# AD9959.net
KiCad netlist of a schematic drawn in Altium Designer
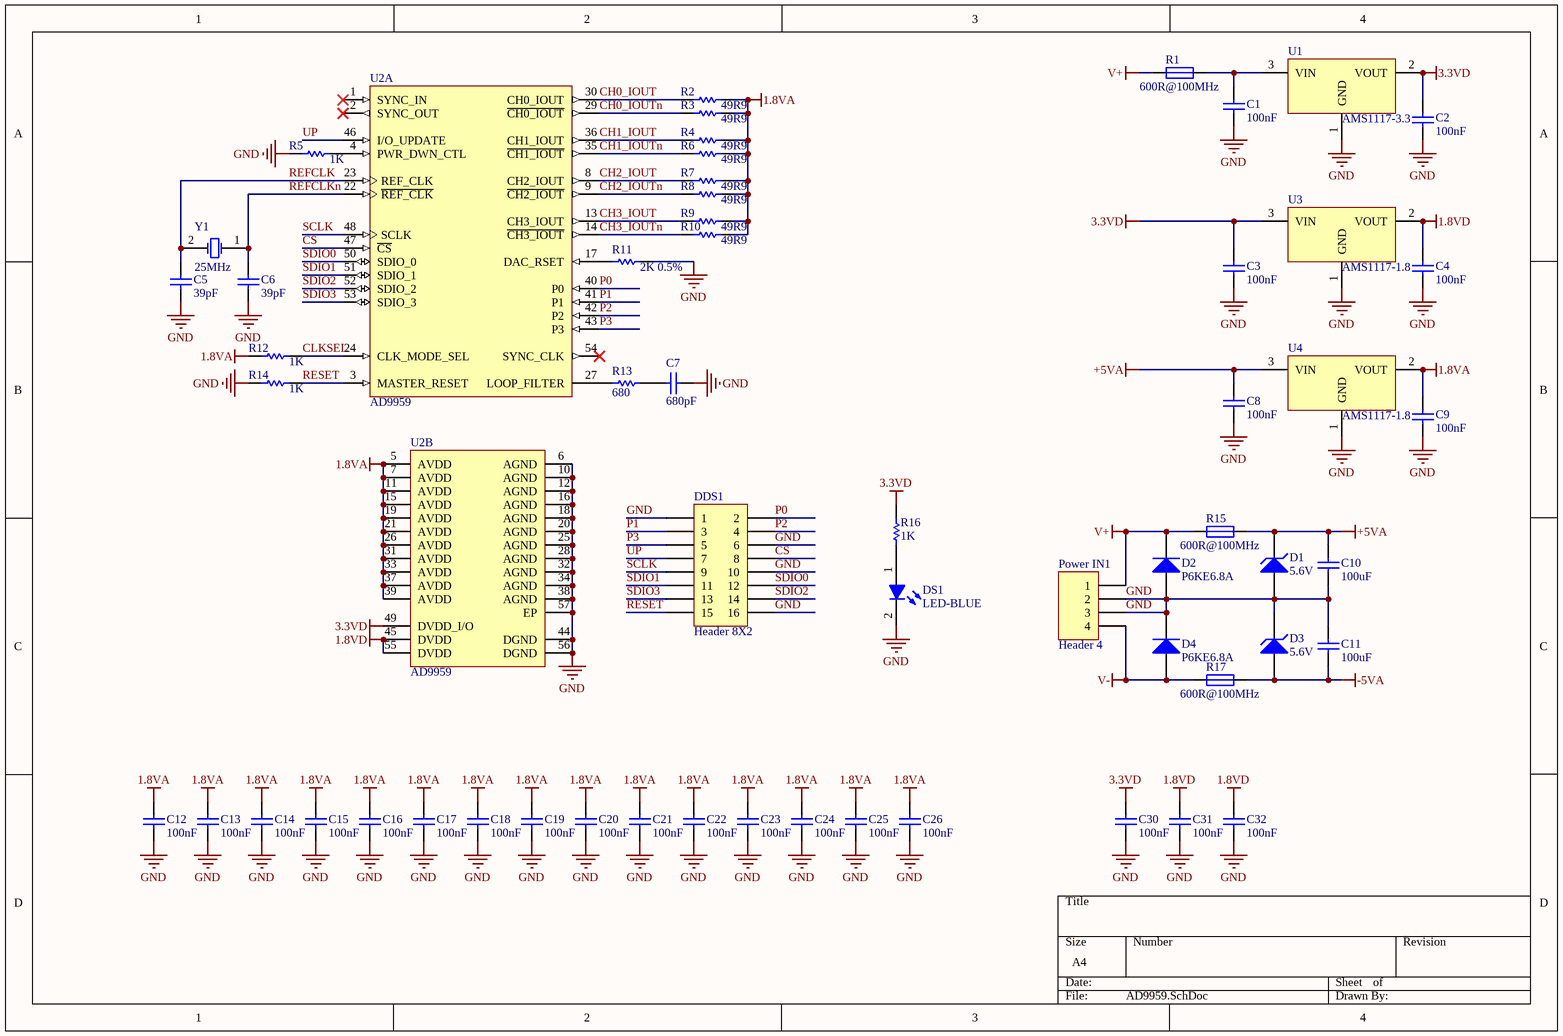
[diagram p0: AD9959.SchDoc]

(export (version "E")
  (design (tool "Eeschema 10.0.6"))
  (components
    (comp (ref "C1")
      (value "100nF")
      (footprint "CAPC0603(1608)55_M")
      (libsource (lib "Slivy's Library") (part "CAP"))
    )
    (comp (ref "C2")
      (value "100nF")
      (footprint "CAPC0603(1608)55_M")
      (libsource (lib "Slivy's Library") (part "CAP"))
    )
    (comp (ref "C3")
      (value "100nF")
      (footprint "CAPC0603(1608)55_M")
      (libsource (lib "Slivy's Library") (part "CAP"))
    )
    (comp (ref "C4")
      (value "100nF")
      (footprint "CAPC0603(1608)55_M")
      (libsource (lib "Slivy's Library") (part "CAP"))
    )
    (comp (ref "C5")
      (value "39pF")
      (footprint "CAPC0603(1608)55_M")
      (libsource (lib "Slivy's Library") (part "CAP"))
    )
    (comp (ref "C6")
      (value "39pF")
      (footprint "CAPC0603(1608)55_M")
      (libsource (lib "Slivy's Library") (part "CAP"))
    )
    (comp (ref "C7")
      (value "680pF")
      (footprint "CAPC0603(1608)55_M")
      (libsource (lib "Slivy's Library") (part "CAP"))
    )
    (comp (ref "C8")
      (value "100nF")
      (footprint "CAPC0603(1608)55_M")
      (libsource (lib "Slivy's Library") (part "CAP"))
    )
    (comp (ref "C9")
      (value "100nF")
      (footprint "CAPC0603(1608)55_M")
      (libsource (lib "Slivy's Library") (part "CAP"))
    )
    (comp (ref "C10") (value "100uF") (footprint "CAPC3225") (libsource (lib "Slivy's Library") (part "CAP")))
    (comp (ref "C11") (value "100uF") (footprint "CAPC3225") (libsource (lib "Slivy's Library") (part "CAP")))
    (comp (ref "C12")
      (value "100nF")
      (footprint "CAPC0603(1608)55_M")
      (libsource (lib "Slivy's Library") (part "CAP"))
    )
    (comp (ref "C13")
      (value "100nF")
      (footprint "CAPC0603(1608)55_M")
      (libsource (lib "Slivy's Library") (part "CAP"))
    )
    (comp (ref "C14")
      (value "100nF")
      (footprint "CAPC0603(1608)55_M")
      (libsource (lib "Slivy's Library") (part "CAP"))
    )
    (comp (ref "C15")
      (value "100nF")
      (footprint "CAPC0603(1608)55_M")
      (libsource (lib "Slivy's Library") (part "CAP"))
    )
    (comp (ref "C16")
      (value "100nF")
      (footprint "CAPC0603(1608)55_M")
      (libsource (lib "Slivy's Library") (part "CAP"))
    )
    (comp (ref "C17")
      (value "100nF")
      (footprint "CAPC0603(1608)55_M")
      (libsource (lib "Slivy's Library") (part "CAP"))
    )
    (comp (ref "C18")
      (value "100nF")
      (footprint "CAPC0603(1608)55_M")
      (libsource (lib "Slivy's Library") (part "CAP"))
    )
    (comp (ref "C19")
      (value "100nF")
      (footprint "CAPC0603(1608)55_M")
      (libsource (lib "Slivy's Library") (part "CAP"))
    )
    (comp (ref "C20")
      (value "100nF")
      (footprint "CAPC0603(1608)55_M")
      (libsource (lib "Slivy's Library") (part "CAP"))
    )
    (comp (ref "C21")
      (value "100nF")
      (footprint "CAPC0603(1608)55_M")
      (libsource (lib "Slivy's Library") (part "CAP"))
    )
    (comp (ref "C22")
      (value "100nF")
      (footprint "CAPC0603(1608)55_M")
      (libsource (lib "Slivy's Library") (part "CAP"))
    )
    (comp (ref "C23")
      (value "100nF")
      (footprint "CAPC0603(1608)55_M")
      (libsource (lib "Slivy's Library") (part "CAP"))
    )
    (comp (ref "C24")
      (value "100nF")
      (footprint "CAPC0603(1608)55_M")
      (libsource (lib "Slivy's Library") (part "CAP"))
    )
    (comp (ref "C25")
      (value "100nF")
      (footprint "CAPC0603(1608)55_M")
      (libsource (lib "Slivy's Library") (part "CAP"))
    )
    (comp (ref "C26")
      (value "100nF")
      (footprint "CAPC0603(1608)55_M")
      (libsource (lib "Slivy's Library") (part "CAP"))
    )
    (comp (ref "C30")
      (value "100nF")
      (footprint "CAPC0603(1608)55_M")
      (libsource (lib "Slivy's Library") (part "CAP"))
    )
    (comp (ref "C31")
      (value "100nF")
      (footprint "CAPC0603(1608)55_M")
      (libsource (lib "Slivy's Library") (part "CAP"))
    )
    (comp (ref "C32")
      (value "100nF")
      (footprint "CAPC0603(1608)55_M")
      (libsource (lib "Slivy's Library") (part "CAP"))
    )
    (comp (ref "D1")
      (value "5.6V")
      (footprint "LL34")
      (description "Zener Diode")
      (fields (field (name "PUBLISHER") "Altium Limited"))
      (libsource (lib "Miscellaneous Devices") (part "D Zener"))
    )
    (comp (ref "D2")
      (value "P6KE6.8A")
      (footprint "DO-214AC")
      (libsource (lib "Slivy's ibrary") (part "Diode"))
    )
    (comp (ref "D3")
      (value "5.6V")
      (footprint "LL34")
      (description "Zener Diode")
      (fields (field (name "PUBLISHER") "Altium Limited"))
      (libsource (lib "Miscellaneous Devices") (part "D Zener"))
    )
    (comp (ref "D4")
      (value "P6KE6.8A")
      (footprint "DO-214AC")
      (libsource (lib "Slivy's ibrary") (part "Diode"))
    )
    (comp (ref "DDS1")
      (value "Header 8X2")
      (footprint "HEADER8X2")
      (description "Header, 8-Pin, Dual row")
      (fields (field (name "PUBLISHER") "Altium Limited"))
      (libsource (lib "Miscellaneous Connectors") (part "Header 8X2"))
    )
    (comp (ref "DS1")
      (value "LED-BLUE")
      (footprint "0603LED_BLUE_V")
      (libsource (lib "Slivy's ibrary") (part "LED-BLUE"))
    )
    (comp (ref "Power IN1")
      (value "Header 4")
      (footprint "3.96-4")
      (description "Header, 4-Pin")
      (fields (field (name "PUBLISHER") "Altium Limited"))
      (libsource (lib "Miscellaneous Connectors") (part "Header 4"))
    )
    (comp (ref "R1")
      (value "600R@100MHz")
      (footprint "Slivy's Library:RESC1206(3216)_M")
      (description "Ferrite Bead")
      (fields
        (field (name "MANUFACTURER") "Generic Components")
        (field (name "PUBLISHER") "Altium Hobart Technology Centre")
      )
      (libsource (lib "Integrated_Library1") (part "Ferrite Bead"))
    )
    (comp (ref "R2")
      (value "49R9")
      (footprint "RESC0603(1608)_M")
      (libsource (lib "Slivy's Library") (part "RES"))
    )
    (comp (ref "R3")
      (value "49R9")
      (footprint "RESC0603(1608)_M")
      (libsource (lib "Slivy's Library") (part "RES"))
    )
    (comp (ref "R4")
      (value "49R9")
      (footprint "RESC0603(1608)_M")
      (libsource (lib "Slivy's Library") (part "RES"))
    )
    (comp (ref "R5")
      (value "1K")
      (footprint "RESC0603(1608)_M")
      (libsource (lib "Slivy's Library") (part "RES"))
    )
    (comp (ref "R6")
      (value "49R9")
      (footprint "RESC0603(1608)_M")
      (libsource (lib "Slivy's Library") (part "RES"))
    )
    (comp (ref "R7")
      (value "49R9")
      (footprint "RESC0603(1608)_M")
      (libsource (lib "Slivy's Library") (part "RES"))
    )
    (comp (ref "R8")
      (value "49R9")
      (footprint "RESC0603(1608)_M")
      (libsource (lib "Slivy's Library") (part "RES"))
    )
    (comp (ref "R9")
      (value "49R9")
      (footprint "RESC0603(1608)_M")
      (libsource (lib "Slivy's Library") (part "RES"))
    )
    (comp (ref "R10")
      (value "49R9")
      (footprint "RESC0603(1608)_M")
      (libsource (lib "Slivy's Library") (part "RES"))
    )
    (comp (ref "R11")
      (value "2K 0.5%")
      (footprint "RESC0603(1608)_M")
      (libsource (lib "Slivy's Library") (part "RES"))
    )
    (comp (ref "R12")
      (value "1K")
      (footprint "RESC0603(1608)_M")
      (libsource (lib "Slivy's Library") (part "RES"))
    )
    (comp (ref "R13")
      (value "680")
      (footprint "RESC0603(1608)_M")
      (libsource (lib "Slivy's Library") (part "RES"))
    )
    (comp (ref "R14")
      (value "1K")
      (footprint "RESC0603(1608)_M")
      (libsource (lib "Slivy's Library") (part "RES"))
    )
    (comp (ref "R15")
      (value "600R@100MHz")
      (footprint "Slivy's Library:RESC1206(3216)_M")
      (description "Ferrite Bead")
      (fields
        (field (name "MANUFACTURER") "Generic Components")
        (field (name "PUBLISHER") "Altium Hobart Technology Centre")
      )
      (libsource (lib "Integrated_Library1") (part "Ferrite Bead"))
    )
    (comp (ref "R16")
      (value "1K")
      (footprint "RESC0603(1608)_M")
      (libsource (lib "Slivy's Library") (part "RES"))
    )
    (comp (ref "R17")
      (value "600R@100MHz")
      (footprint "RESC1206(3216)_M")
      (description "Ferrite Bead")
      (fields
        (field (name "MANUFACTURER") "Generic Components")
        (field (name "PUBLISHER") "Altium Hobart Technology Centre")
      )
      (libsource (lib "Integrated_Library1") (part "Ferrite Bead"))
    )
    (comp (ref "U1")
      (value "AMS1117-3.3")
      (footprint "SOT-223_M")
      (libsource (lib "Slivy's ibrary") (part "AMS1117"))
    )
    (comp (ref "U2") (value "AD9959") (footprint "QFN56") (libsource (lib "Slivy's ibrary") (part "AD9959")))
    (comp (ref "U3")
      (value "AMS1117-1.8")
      (footprint "SOT-223_M")
      (libsource (lib "Slivy's ibrary") (part "AMS1117"))
    )
    (comp (ref "U4")
      (value "AMS1117-1.8")
      (footprint "SOT-223_M")
      (libsource (lib "Slivy's ibrary") (part "AMS1117"))
    )
    (comp (ref "Y1")
      (value "25MHz")
      (footprint "HC-49S")
      (description "Crystal Oscillator")
      (fields (field (name "PUBLISHER") "Altium Limited"))
      (libsource (lib "Slivy's ibrary") (part "XTAL"))
    )
  )
  (nets
    (net (code "1") (name "+5VA") (class "Default")
      (node (ref "C10") (pin "2") (pinfunction "2_2") (pintype "passive"))
      (node (ref "C8") (pin "2") (pinfunction "2_2") (pintype "passive"))
      (node (ref "D1") (pin "2") (pinfunction "K_2") (pintype "passive"))
      (node (ref "R15") (pin "2") (pinfunction "2_2") (pintype "passive"))
      (node (ref "U4") (pin "3") (pinfunction "VIN_3") (pintype "power_in"))
    )
    (net (code "2") (name "-5VA") (class "Default")
      (node (ref "C11") (pin "2") (pinfunction "2_2") (pintype "passive"))
      (node (ref "D3") (pin "1") (pinfunction "A_1") (pintype "passive"))
      (node (ref "R17") (pin "2") (pinfunction "2_2") (pintype "passive"))
    )
    (net (code "3") (name "/CH0_IOUT") (class "Default")
      (node (ref "R2") (pin "1") (pinfunction "1_1") (pintype "passive"))
      (node (ref "U2") (pin "30") (pinfunction "CH0_IOUT_30") (pintype "output"))
    )
    (net (code "4") (name "/CH0_IOUTn") (class "Default")
      (node (ref "R3") (pin "1") (pinfunction "1_1") (pintype "passive"))
      (node (ref "U2") (pin "29") (pinfunction "~{CH0_IOUT}_29") (pintype "output"))
    )
    (net (code "5") (name "/CH1_IOUT") (class "Default")
      (node (ref "R4") (pin "1") (pinfunction "1_1") (pintype "passive"))
      (node (ref "U2") (pin "36") (pinfunction "CH1_IOUT_36") (pintype "output"))
    )
    (net (code "6") (name "/CH1_IOUTn") (class "Default")
      (node (ref "R6") (pin "1") (pinfunction "1_1") (pintype "passive"))
      (node (ref "U2") (pin "35") (pinfunction "~{CH1_IOUT}_35") (pintype "output"))
    )
    (net (code "7") (name "/CH2_IOUT") (class "Default")
      (node (ref "R7") (pin "1") (pinfunction "1_1") (pintype "passive"))
      (node (ref "U2") (pin "8") (pinfunction "CH2_IOUT_8") (pintype "output"))
    )
    (net (code "8") (name "/CH2_IOUTn") (class "Default")
      (node (ref "R8") (pin "1") (pinfunction "1_1") (pintype "passive"))
      (node (ref "U2") (pin "9") (pinfunction "~{CH2_IOUT}_9") (pintype "output"))
    )
    (net (code "9") (name "/CH3_IOUT") (class "Default")
      (node (ref "R9") (pin "1") (pinfunction "1_1") (pintype "passive"))
      (node (ref "U2") (pin "13") (pinfunction "CH3_IOUT_13") (pintype "output"))
    )
    (net (code "10") (name "/CH3_IOUTn") (class "Default")
      (node (ref "R10") (pin "1") (pinfunction "1_1") (pintype "passive"))
      (node (ref "U2") (pin "14") (pinfunction "~{CH3_IOUT}_14") (pintype "output"))
    )
    (net (code "11") (name "/CLKSEL") (class "Default")
      (node (ref "R12") (pin "2") (pinfunction "2_2") (pintype "passive"))
      (node (ref "U2") (pin "24") (pinfunction "CLK_MODE_SEL_24") (pintype "input"))
    )
    (net (code "12") (name "/CS") (class "Default")
      (node (ref "DDS1") (pin "8") (pinfunction "8_8") (pintype "passive"))
      (node (ref "U2") (pin "47") (pinfunction "~{CS}_47") (pintype "input"))
    )
    (net (code "13") (name "/P0") (class "Default")
      (node (ref "DDS1") (pin "2") (pinfunction "2_2") (pintype "passive"))
      (node (ref "U2") (pin "40") (pinfunction "P0_40") (pintype "input"))
    )
    (net (code "14") (name "/P1") (class "Default")
      (node (ref "DDS1") (pin "3") (pinfunction "3_3") (pintype "passive"))
      (node (ref "U2") (pin "41") (pinfunction "P1_41") (pintype "input"))
    )
    (net (code "15") (name "/P2") (class "Default")
      (node (ref "DDS1") (pin "4") (pinfunction "4_4") (pintype "passive"))
      (node (ref "U2") (pin "42") (pinfunction "P2_42") (pintype "input"))
    )
    (net (code "16") (name "/P3") (class "Default")
      (node (ref "DDS1") (pin "5") (pinfunction "5_5") (pintype "passive"))
      (node (ref "U2") (pin "43") (pinfunction "P3_43") (pintype "input"))
    )
    (net (code "17") (name "/REFCLK") (class "Default")
      (node (ref "C5") (pin "2") (pinfunction "2_2") (pintype "passive"))
      (node (ref "U2") (pin "23") (pinfunction "REF_CLK_23") (pintype "input"))
      (node (ref "Y1") (pin "2") (pinfunction "OSC2_2") (pintype "passive"))
    )
    (net (code "18") (name "/REFCLKn") (class "Default")
      (node (ref "C6") (pin "2") (pinfunction "2_2") (pintype "passive"))
      (node (ref "U2") (pin "22") (pinfunction "~{REF_CLK}_22") (pintype "input"))
      (node (ref "Y1") (pin "1") (pinfunction "OSC1_1") (pintype "passive"))
    )
    (net (code "19") (name "/RESET") (class "Default")
      (node (ref "DDS1") (pin "15") (pinfunction "15_15") (pintype "passive"))
      (node (ref "R14") (pin "2") (pinfunction "2_2") (pintype "passive"))
      (node (ref "U2") (pin "3") (pinfunction "MASTER_RESET_3") (pintype "input"))
    )
    (net (code "20") (name "/SCLK") (class "Default")
      (node (ref "DDS1") (pin "9") (pinfunction "9_9") (pintype "passive"))
      (node (ref "U2") (pin "48") (pinfunction "SCLK_48") (pintype "input"))
    )
    (net (code "21") (name "/SDIO0") (class "Default")
      (node (ref "DDS1") (pin "12") (pinfunction "12_12") (pintype "passive"))
      (node (ref "U2") (pin "50") (pinfunction "SDIO_0_50") (pintype "bidirectional"))
    )
    (net (code "22") (name "/SDIO1") (class "Default")
      (node (ref "DDS1") (pin "11") (pinfunction "11_11") (pintype "passive"))
      (node (ref "U2") (pin "51") (pinfunction "SDIO_1_51") (pintype "bidirectional"))
    )
    (net (code "23") (name "/SDIO2") (class "Default")
      (node (ref "DDS1") (pin "14") (pinfunction "14_14") (pintype "passive"))
      (node (ref "U2") (pin "52") (pinfunction "SDIO_2_52") (pintype "bidirectional"))
    )
    (net (code "24") (name "/SDIO3") (class "Default")
      (node (ref "DDS1") (pin "13") (pinfunction "13_13") (pintype "passive"))
      (node (ref "U2") (pin "53") (pinfunction "SDIO_3_53") (pintype "bidirectional"))
    )
    (net (code "25") (name "/UP") (class "Default")
      (node (ref "DDS1") (pin "7") (pinfunction "7_7") (pintype "passive"))
      (node (ref "U2") (pin "46") (pinfunction "I/O_UPDATE_46") (pintype "input"))
    )
    (net (code "26") (name "1.8VA") (class "Default")
      (node (ref "C12") (pin "2") (pinfunction "2_2") (pintype "passive"))
      (node (ref "C13") (pin "2") (pinfunction "2_2") (pintype "passive"))
      (node (ref "C14") (pin "2") (pinfunction "2_2") (pintype "passive"))
      (node (ref "C15") (pin "2") (pinfunction "2_2") (pintype "passive"))
      (node (ref "C16") (pin "2") (pinfunction "2_2") (pintype "passive"))
      (node (ref "C17") (pin "2") (pinfunction "2_2") (pintype "passive"))
      (node (ref "C18") (pin "2") (pinfunction "2_2") (pintype "passive"))
      (node (ref "C19") (pin "2") (pinfunction "2_2") (pintype "passive"))
      (node (ref "C20") (pin "2") (pinfunction "2_2") (pintype "passive"))
      (node (ref "C21") (pin "2") (pinfunction "2_2") (pintype "passive"))
      (node (ref "C22") (pin "2") (pinfunction "2_2") (pintype "passive"))
      (node (ref "C23") (pin "2") (pinfunction "2_2") (pintype "passive"))
      (node (ref "C24") (pin "2") (pinfunction "2_2") (pintype "passive"))
      (node (ref "C25") (pin "2") (pinfunction "2_2") (pintype "passive"))
      (node (ref "C26") (pin "2") (pinfunction "2_2") (pintype "passive"))
      (node (ref "C9") (pin "2") (pinfunction "2_2") (pintype "passive"))
      (node (ref "R10") (pin "2") (pinfunction "2_2") (pintype "passive"))
      (node (ref "R12") (pin "1") (pinfunction "1_1") (pintype "passive"))
      (node (ref "R2") (pin "2") (pinfunction "2_2") (pintype "passive"))
      (node (ref "R3") (pin "2") (pinfunction "2_2") (pintype "passive"))
      (node (ref "R4") (pin "2") (pinfunction "2_2") (pintype "passive"))
      (node (ref "R6") (pin "2") (pinfunction "2_2") (pintype "passive"))
      (node (ref "R7") (pin "2") (pinfunction "2_2") (pintype "passive"))
      (node (ref "R8") (pin "2") (pinfunction "2_2") (pintype "passive"))
      (node (ref "R9") (pin "2") (pinfunction "2_2") (pintype "passive"))
      (node (ref "U2") (pin "11") (pinfunction "AVDD_11") (pintype "power_in"))
      (node (ref "U2") (pin "15") (pinfunction "AVDD_15") (pintype "power_in"))
      (node (ref "U2") (pin "19") (pinfunction "AVDD_19") (pintype "power_in"))
      (node (ref "U2") (pin "21") (pinfunction "AVDD_21") (pintype "power_in"))
      (node (ref "U2") (pin "26") (pinfunction "AVDD_26") (pintype "power_in"))
      (node (ref "U2") (pin "31") (pinfunction "AVDD_31") (pintype "power_in"))
      (node (ref "U2") (pin "33") (pinfunction "AVDD_33") (pintype "power_in"))
      (node (ref "U2") (pin "37") (pinfunction "AVDD_37") (pintype "power_in"))
      (node (ref "U2") (pin "39") (pinfunction "AVDD_39") (pintype "power_in"))
      (node (ref "U2") (pin "5") (pinfunction "AVDD_5") (pintype "power_in"))
      (node (ref "U2") (pin "7") (pinfunction "AVDD_7") (pintype "power_in"))
      (node (ref "U4") (pin "2") (pinfunction "VOUT_2") (pintype "power_in"))
    )
    (net (code "27") (name "1.8VD") (class "Default")
      (node (ref "C31") (pin "2") (pinfunction "2_2") (pintype "passive"))
      (node (ref "C32") (pin "2") (pinfunction "2_2") (pintype "passive"))
      (node (ref "C4") (pin "2") (pinfunction "2_2") (pintype "passive"))
      (node (ref "U2") (pin "45") (pinfunction "DVDD_45") (pintype "power_in"))
      (node (ref "U2") (pin "55") (pinfunction "DVDD_55") (pintype "power_in"))
      (node (ref "U3") (pin "2") (pinfunction "VOUT_2") (pintype "power_in"))
    )
    (net (code "28") (name "3.3VD") (class "Default")
      (node (ref "C2") (pin "2") (pinfunction "2_2") (pintype "passive"))
      (node (ref "C3") (pin "2") (pinfunction "2_2") (pintype "passive"))
      (node (ref "C30") (pin "2") (pinfunction "2_2") (pintype "passive"))
      (node (ref "R16") (pin "2") (pinfunction "2_2") (pintype "passive"))
      (node (ref "U1") (pin "2") (pinfunction "VOUT_2") (pintype "power_in"))
      (node (ref "U2") (pin "49") (pinfunction "DVDD_I/O_49") (pintype "power_in"))
      (node (ref "U3") (pin "3") (pinfunction "VIN_3") (pintype "power_in"))
    )
    (net (code "29") (name "GND") (class "Default")
      (node (ref "C1") (pin "1") (pinfunction "1_1") (pintype "passive"))
      (node (ref "C10") (pin "1") (pinfunction "1_1") (pintype "passive"))
      (node (ref "C11") (pin "1") (pinfunction "1_1") (pintype "passive"))
      (node (ref "C12") (pin "1") (pinfunction "1_1") (pintype "passive"))
      (node (ref "C13") (pin "1") (pinfunction "1_1") (pintype "passive"))
      (node (ref "C14") (pin "1") (pinfunction "1_1") (pintype "passive"))
      (node (ref "C15") (pin "1") (pinfunction "1_1") (pintype "passive"))
      (node (ref "C16") (pin "1") (pinfunction "1_1") (pintype "passive"))
      (node (ref "C17") (pin "1") (pinfunction "1_1") (pintype "passive"))
      (node (ref "C18") (pin "1") (pinfunction "1_1") (pintype "passive"))
      (node (ref "C19") (pin "1") (pinfunction "1_1") (pintype "passive"))
      (node (ref "C2") (pin "1") (pinfunction "1_1") (pintype "passive"))
      (node (ref "C20") (pin "1") (pinfunction "1_1") (pintype "passive"))
      (node (ref "C21") (pin "1") (pinfunction "1_1") (pintype "passive"))
      (node (ref "C22") (pin "1") (pinfunction "1_1") (pintype "passive"))
      (node (ref "C23") (pin "1") (pinfunction "1_1") (pintype "passive"))
      (node (ref "C24") (pin "1") (pinfunction "1_1") (pintype "passive"))
      (node (ref "C25") (pin "1") (pinfunction "1_1") (pintype "passive"))
      (node (ref "C26") (pin "1") (pinfunction "1_1") (pintype "passive"))
      (node (ref "C3") (pin "1") (pinfunction "1_1") (pintype "passive"))
      (node (ref "C30") (pin "1") (pinfunction "1_1") (pintype "passive"))
      (node (ref "C31") (pin "1") (pinfunction "1_1") (pintype "passive"))
      (node (ref "C32") (pin "1") (pinfunction "1_1") (pintype "passive"))
      (node (ref "C4") (pin "1") (pinfunction "1_1") (pintype "passive"))
      (node (ref "C5") (pin "1") (pinfunction "1_1") (pintype "passive"))
      (node (ref "C6") (pin "1") (pinfunction "1_1") (pintype "passive"))
      (node (ref "C7") (pin "2") (pinfunction "2_2") (pintype "passive"))
      (node (ref "C8") (pin "1") (pinfunction "1_1") (pintype "passive"))
      (node (ref "C9") (pin "1") (pinfunction "1_1") (pintype "passive"))
      (node (ref "D1") (pin "1") (pinfunction "A_1") (pintype "passive"))
      (node (ref "D2") (pin "2") (pinfunction "A_2") (pintype "passive"))
      (node (ref "D3") (pin "2") (pinfunction "K_2") (pintype "passive"))
      (node (ref "D4") (pin "1") (pinfunction "K_1") (pintype "passive"))
      (node (ref "DDS1") (pin "1") (pinfunction "1_1") (pintype "passive"))
      (node (ref "DDS1") (pin "10") (pinfunction "10_10") (pintype "passive"))
      (node (ref "DDS1") (pin "16") (pinfunction "16_16") (pintype "passive"))
      (node (ref "DDS1") (pin "6") (pinfunction "6_6") (pintype "passive"))
      (node (ref "DS1") (pin "2") (pinfunction "K_2") (pintype "passive"))
      (node (ref "Power IN1") (pin "2") (pinfunction "2_2") (pintype "passive"))
      (node (ref "Power IN1") (pin "3") (pinfunction "3_3") (pintype "passive"))
      (node (ref "R11") (pin "2") (pinfunction "2_2") (pintype "passive"))
      (node (ref "R14") (pin "1") (pinfunction "1_1") (pintype "passive"))
      (node (ref "R5") (pin "1") (pinfunction "1_1") (pintype "passive"))
      (node (ref "U1") (pin "1") (pinfunction "GND_1") (pintype "power_in"))
      (node (ref "U2") (pin "10") (pinfunction "AGND_10") (pintype "power_in"))
      (node (ref "U2") (pin "12") (pinfunction "AGND_12") (pintype "power_in"))
      (node (ref "U2") (pin "16") (pinfunction "AGND_16") (pintype "power_in"))
      (node (ref "U2") (pin "18") (pinfunction "AGND_18") (pintype "power_in"))
      (node (ref "U2") (pin "20") (pinfunction "AGND_20") (pintype "power_in"))
      (node (ref "U2") (pin "25") (pinfunction "AGND_25") (pintype "power_in"))
      (node (ref "U2") (pin "28") (pinfunction "AGND_28") (pintype "power_in"))
      (node (ref "U2") (pin "32") (pinfunction "AGND_32") (pintype "power_in"))
      (node (ref "U2") (pin "34") (pinfunction "AGND_34") (pintype "power_in"))
      (node (ref "U2") (pin "38") (pinfunction "AGND_38") (pintype "power_in"))
      (node (ref "U2") (pin "44") (pinfunction "DGND_44") (pintype "power_in"))
      (node (ref "U2") (pin "56") (pinfunction "DGND_56") (pintype "power_in"))
      (node (ref "U2") (pin "57") (pinfunction "EP_57") (pintype "power_in"))
      (node (ref "U2") (pin "6") (pinfunction "AGND_6") (pintype "power_in"))
      (node (ref "U3") (pin "1") (pinfunction "GND_1") (pintype "power_in"))
      (node (ref "U4") (pin "1") (pinfunction "GND_1") (pintype "power_in"))
    )
    (net (code "30") (name "Net-(C7-Pad1)") (class "Default")
      (node (ref "C7") (pin "1") (pinfunction "1_1") (pintype "passive"))
      (node (ref "R13") (pin "2") (pinfunction "2_2") (pintype "passive"))
    )
    (net (code "31") (name "Net-(DS1-A)") (class "Default")
      (node (ref "DS1") (pin "1") (pinfunction "A_1") (pintype "passive"))
      (node (ref "R16") (pin "1") (pinfunction "1_1") (pintype "passive"))
    )
    (net (code "32") (name "Net-(U1-VIN)") (class "Default")
      (node (ref "C1") (pin "2") (pinfunction "2_2") (pintype "passive"))
      (node (ref "R1") (pin "2") (pinfunction "2_2") (pintype "passive"))
      (node (ref "U1") (pin "3") (pinfunction "VIN_3") (pintype "power_in"))
    )
    (net (code "33") (name "Net-(U2A-DAC_RSET)") (class "Default")
      (node (ref "R11") (pin "1") (pinfunction "1_1") (pintype "passive"))
      (node (ref "U2") (pin "17") (pinfunction "DAC_RSET_17") (pintype "input"))
    )
    (net (code "34") (name "Net-(U2A-LOOP_FILTER)") (class "Default")
      (node (ref "R13") (pin "1") (pinfunction "1_1") (pintype "passive"))
      (node (ref "U2") (pin "27") (pinfunction "LOOP_FILTER_27") (pintype "passive"))
    )
    (net (code "35") (name "Net-(U2A-PWR_DWN_CTL)") (class "Default")
      (node (ref "R5") (pin "2") (pinfunction "2_2") (pintype "passive"))
      (node (ref "U2") (pin "4") (pinfunction "PWR_DWN_CTL_4") (pintype "input"))
    )
    (net (code "36") (name "V+") (class "Default")
      (node (ref "D2") (pin "1") (pinfunction "K_1") (pintype "passive"))
      (node (ref "Power IN1") (pin "1") (pinfunction "1_1") (pintype "passive"))
      (node (ref "R1") (pin "1") (pinfunction "1_1") (pintype "passive"))
      (node (ref "R15") (pin "1") (pinfunction "1_1") (pintype "passive"))
    )
    (net (code "37") (name "V-") (class "Default")
      (node (ref "D4") (pin "2") (pinfunction "A_2") (pintype "passive"))
      (node (ref "Power IN1") (pin "4") (pinfunction "4_4") (pintype "passive"))
      (node (ref "R17") (pin "1") (pinfunction "1_1") (pintype "passive"))
    )
    (net (code "38") (name "unconnected-(U2A-SYNC_CLK-Pad54)") (class "Default")
      (node (ref "U2") (pin "54") (pinfunction "SYNC_CLK_54") (pintype "output+no_connect"))
    )
    (net (code "39") (name "unconnected-(U2A-SYNC_IN-Pad1)") (class "Default")
      (node (ref "U2") (pin "1") (pinfunction "SYNC_IN_1") (pintype "input+no_connect"))
    )
    (net (code "40") (name "unconnected-(U2A-SYNC_OUT-Pad2)") (class "Default")
      (node (ref "U2") (pin "2") (pinfunction "SYNC_OUT_2") (pintype "output+no_connect"))
    )
  )
)
